# LED_driverV1.net
KiCad netlist of a schematic drawn in EAGLE
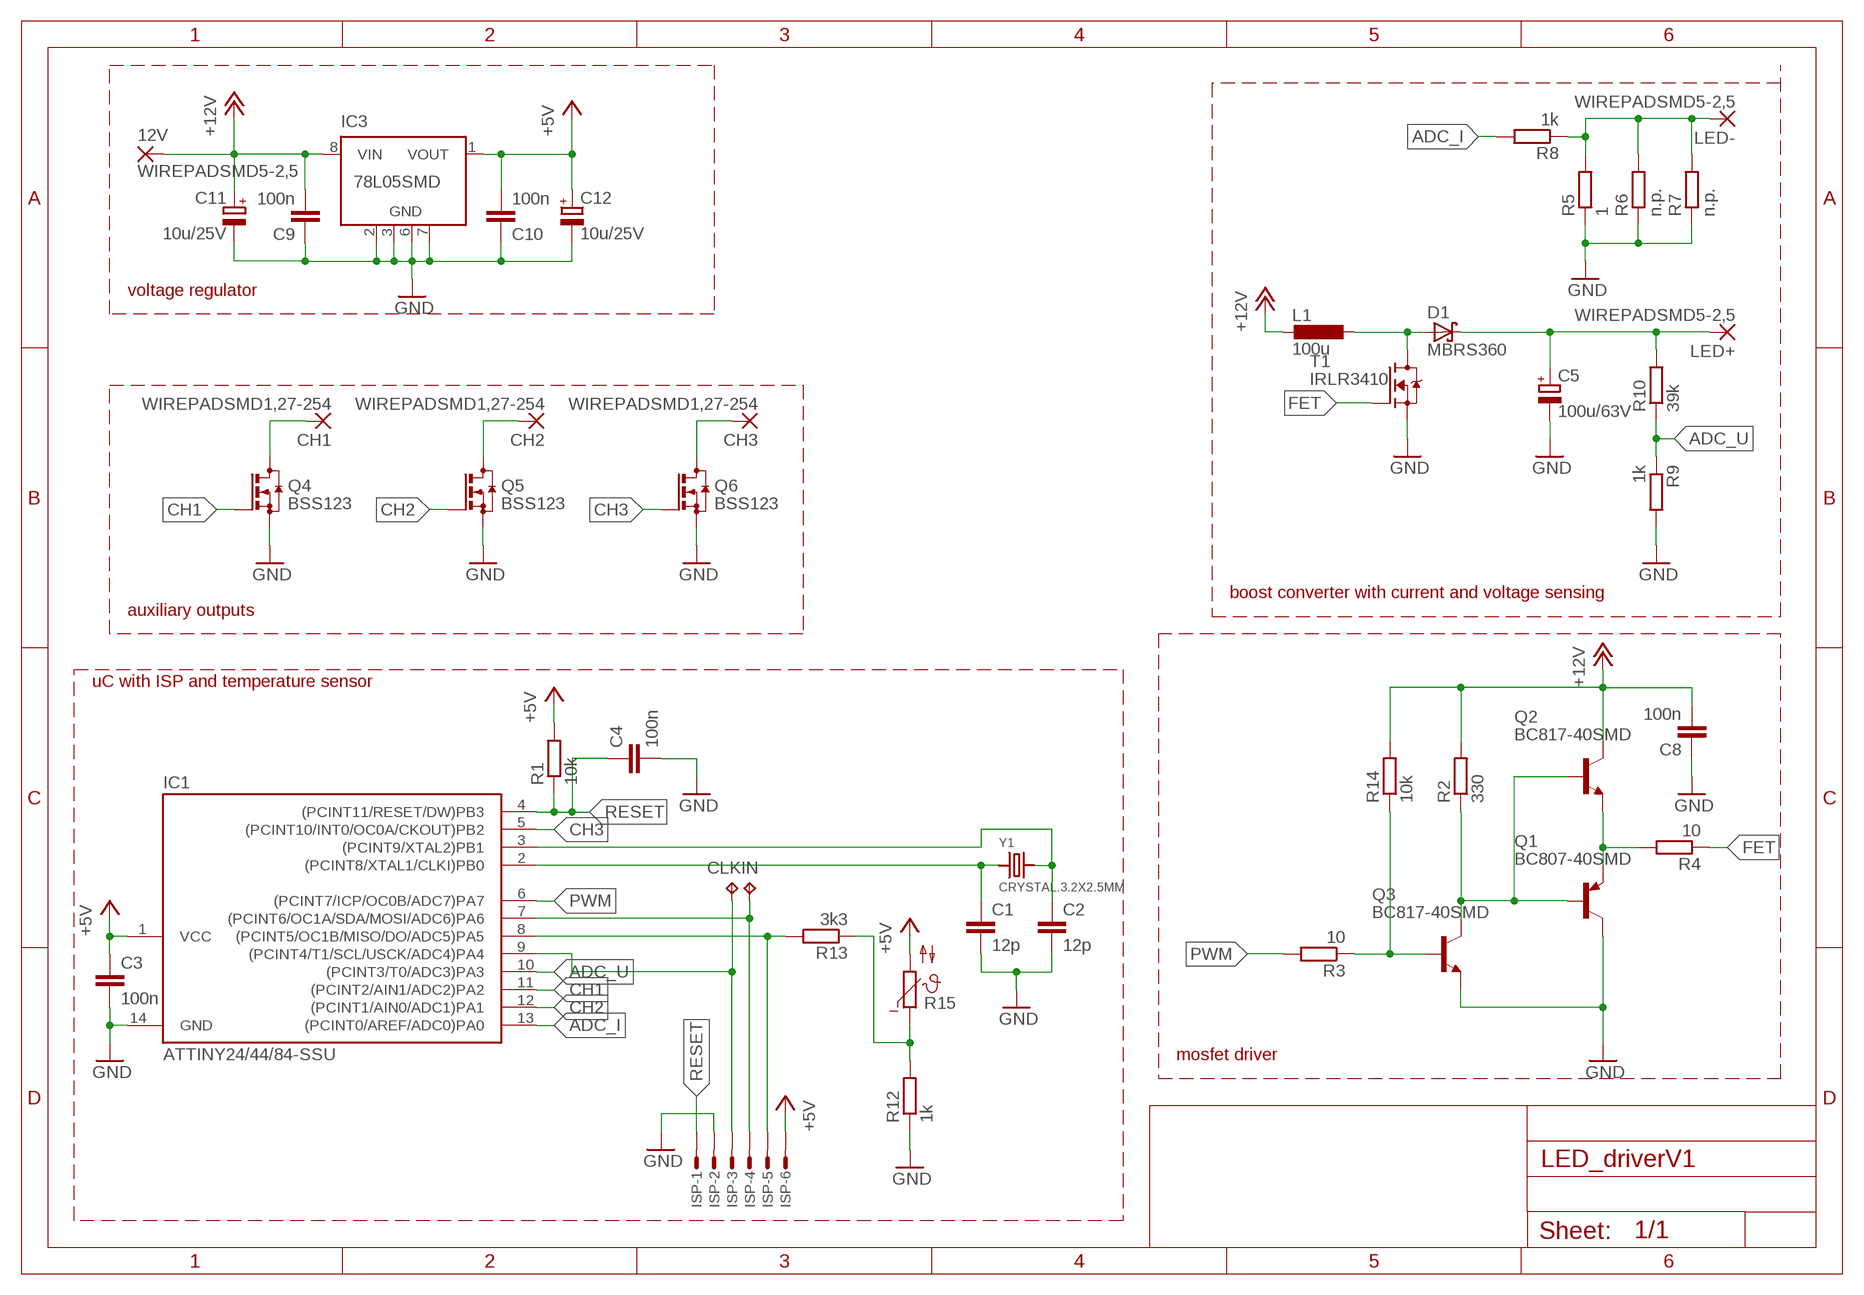
[diagram p0: schematic, sheet 1]

(export (version "E")
  (design (tool "Eeschema 10.0.6"))
  (components
    (comp (ref "12V")
      (value "WIREPADSMD5-2,5")
      (footprint "eagle-import:5-2,5")
      (libsource (lib "eagle-import") (part "WIREPADSMD5-2,5"))
    )
    (comp (ref "C1")
      (value "12p")
      (footprint "eagle-import:C0603K")
      (libsource (lib "eagle-import") (part "C-EUC0603K"))
    )
    (comp (ref "C2")
      (value "12p")
      (footprint "eagle-import:C0603K")
      (libsource (lib "eagle-import") (part "C-EUC0603K"))
    )
    (comp (ref "C3")
      (value "100n")
      (footprint "eagle-import:C0603K")
      (libsource (lib "eagle-import") (part "C-EUC0603K"))
    )
    (comp (ref "C4")
      (value "100n")
      (footprint "eagle-import:C0603K")
      (libsource (lib "eagle-import") (part "C-EUC0603K"))
    )
    (comp (ref "C5")
      (value "100u/63V")
      (footprint "eagle-import:153CLV-1010")
      (libsource (lib "eagle-import") (part "CPOL-EU153CLV-1010"))
    )
    (comp (ref "C8")
      (value "100n")
      (footprint "eagle-import:C0603K")
      (libsource (lib "eagle-import") (part "C-EUC0603K"))
    )
    (comp (ref "C9")
      (value "100n")
      (footprint "eagle-import:C0603K")
      (libsource (lib "eagle-import") (part "C-EUC0603K"))
    )
    (comp (ref "C10")
      (value "100n")
      (footprint "eagle-import:C0603K")
      (libsource (lib "eagle-import") (part "C-EUC0603K"))
    )
    (comp (ref "C11")
      (value "10u/25V")
      (footprint "eagle-import:153CLV-0405")
      (libsource (lib "eagle-import") (part "CPOL-EU153CLV-0405"))
    )
    (comp (ref "C12")
      (value "10u/25V")
      (footprint "eagle-import:153CLV-0405")
      (libsource (lib "eagle-import") (part "CPOL-EU153CLV-0405"))
    )
    (comp (ref "CH1")
      (value "WIREPADSMD1,27-254")
      (footprint "eagle-import:SMD1,27-2,54")
      (libsource (lib "eagle-import") (part "WIREPADSMD1,27-254"))
    )
    (comp (ref "CH2")
      (value "WIREPADSMD1,27-254")
      (footprint "eagle-import:SMD1,27-2,54")
      (libsource (lib "eagle-import") (part "WIREPADSMD1,27-254"))
    )
    (comp (ref "CH3")
      (value "WIREPADSMD1,27-254")
      (footprint "eagle-import:SMD1,27-2,54")
      (libsource (lib "eagle-import") (part "WIREPADSMD1,27-254"))
    )
    (comp (ref "CLK")
      (value "TPTP15R")
      (footprint "eagle-import:TP15R")
      (libsource (lib "eagle-import") (part "TPTP15R"))
    )
    (comp (ref "D1")
      (value "MBRS360")
      (footprint "eagle-import:SMC")
      (libsource (lib "eagle-import") (part "SCHOTTKY-DIODESMC"))
    )
    (comp (ref "IC1")
      (value "ATTINY24/44/84-SSU")
      (footprint "eagle-import:SOIC14")
      (libsource (lib "eagle-import") (part "ATTINY24/44/84-SSU"))
    )
    (comp (ref "IC3")
      (value "78L05SMD")
      (footprint "eagle-import:SO08")
      (libsource (lib "eagle-import") (part "78LSMD05"))
    )
    (comp (ref "IN")
      (value "TPTP15R")
      (footprint "eagle-import:TP15R")
      (libsource (lib "eagle-import") (part "TPTP15R"))
    )
    (comp (ref "ISP")
      (value "MICROMATCH-6SMF")
      (footprint "eagle-import:MMT-F-SMD-6")
      (libsource (lib "eagle-import") (part "MICROMATCH-6SMF"))
    )
    (comp (ref "L1")
      (value "100u")
      (footprint "eagle-import:PISM")
      (libsource (lib "eagle-import") (part "L-EUPISM"))
    )
    (comp (ref "LED+")
      (value "WIREPADSMD5-2,5")
      (footprint "eagle-import:5-2,5")
      (libsource (lib "eagle-import") (part "WIREPADSMD5-2,5"))
    )
    (comp (ref "LED-")
      (value "WIREPADSMD5-2,5")
      (footprint "eagle-import:5-2,5")
      (libsource (lib "eagle-import") (part "WIREPADSMD5-2,5"))
    )
    (comp (ref "Q1")
      (value "BC807-40SMD")
      (footprint "eagle-import:SOT23-BEC")
      (libsource (lib "eagle-import") (part "BC807SMD-40"))
    )
    (comp (ref "Q2")
      (value "BC817-40SMD")
      (footprint "eagle-import:SOT23-BEC")
      (libsource (lib "eagle-import") (part "BC817SMD-40"))
    )
    (comp (ref "Q3")
      (value "BC817-40SMD")
      (footprint "eagle-import:SOT23-BEC")
      (libsource (lib "eagle-import") (part "BC817SMD-40"))
    )
    (comp (ref "Q4")
      (value "BSS123")
      (footprint "eagle-import:SOT23")
      (libsource (lib "eagle-import") (part "BSS123"))
    )
    (comp (ref "Q5")
      (value "BSS123")
      (footprint "eagle-import:SOT23")
      (libsource (lib "eagle-import") (part "BSS123"))
    )
    (comp (ref "Q6")
      (value "BSS123")
      (footprint "eagle-import:SOT23")
      (libsource (lib "eagle-import") (part "BSS123"))
    )
    (comp (ref "R1")
      (value "10k")
      (footprint "eagle-import:R0603")
      (libsource (lib "eagle-import") (part "R-EU_R0603"))
    )
    (comp (ref "R2")
      (value "330")
      (footprint "eagle-import:R0603")
      (libsource (lib "eagle-import") (part "R-EU_R0603"))
    )
    (comp (ref "R3")
      (value "10")
      (footprint "eagle-import:R0603")
      (libsource (lib "eagle-import") (part "R-EU_R0603"))
    )
    (comp (ref "R4")
      (value "10")
      (footprint "eagle-import:R0603")
      (libsource (lib "eagle-import") (part "R-EU_R0603"))
    )
    (comp (ref "R5")
      (value "1")
      (footprint "eagle-import:R1206")
      (libsource (lib "eagle-import") (part "resistor_R-EU_R1206"))
    )
    (comp (ref "R6")
      (value "n.p.")
      (footprint "eagle-import:R1206")
      (libsource (lib "eagle-import") (part "resistor_R-EU_R1206"))
    )
    (comp (ref "R7")
      (value "n.p.")
      (footprint "eagle-import:R1206")
      (libsource (lib "eagle-import") (part "resistor_R-EU_R1206"))
    )
    (comp (ref "R8")
      (value "1k")
      (footprint "eagle-import:R0603")
      (libsource (lib "eagle-import") (part "R-EU_R0603"))
    )
    (comp (ref "R9")
      (value "1k")
      (footprint "eagle-import:R0603")
      (libsource (lib "eagle-import") (part "R-EU_R0603"))
    )
    (comp (ref "R10")
      (value "39k")
      (footprint "eagle-import:R0603")
      (libsource (lib "eagle-import") (part "R-EU_R0603"))
    )
    (comp (ref "R12")
      (value "1k")
      (footprint "eagle-import:R0603")
      (libsource (lib "eagle-import") (part "R-EU_R0603"))
    )
    (comp (ref "R13")
      (value "3k3")
      (footprint "eagle-import:R0603")
      (libsource (lib "eagle-import") (part "R-EU_R0603"))
    )
    (comp (ref "R14")
      (value "10k")
      (footprint "eagle-import:R0603")
      (libsource (lib "eagle-import") (part "R-EU_R0603"))
    )
    (comp (ref "R15")
      (value "NTC640")
      (footprint "eagle-import:P640")
      (libsource (lib "eagle-import") (part "NTC640"))
    )
    (comp (ref "T1")
      (value "IRLR3410")
      (footprint "eagle-import:TO252")
      (libsource (lib "eagle-import") (part "IRLR3410"))
    )
    (comp (ref "Y1")
      (value "CRYSTAL.3.2X2.5MM")
      (footprint "eagle-import:3.2X2.5MM")
      (libsource (lib "eagle-import") (part "CRYSTAL.3.2X2.5MM"))
    )
  )
  (nets
    (net (code "1") (name "+5V") (class "Default")
      (node (ref "C10") (pin "2") (pinfunction "2_2") (pintype "passive"))
      (node (ref "C12") (pin "+") (pinfunction "+_+") (pintype "passive"))
      (node (ref "C3") (pin "1") (pinfunction "1_1") (pintype "passive"))
      (node (ref "IC1") (pin "1") (pinfunction "VCC_1") (pintype "power_in"))
      (node (ref "IC3") (pin "1") (pinfunction "VOUT_1") (pintype "output"))
      (node (ref "ISP") (pin "6") (pinfunction "S_6") (pintype "passive"))
      (node (ref "R1") (pin "2") (pinfunction "2_2") (pintype "passive"))
      (node (ref "R15") (pin "2") (pinfunction "2_2") (pintype "passive"))
    )
    (net (code "2") (name "+12V") (class "Default")
      (node (ref "12V") (pin "1") (pinfunction "P_1") (pintype "passive"))
      (node (ref "C11") (pin "+") (pinfunction "+_+") (pintype "passive"))
      (node (ref "C8") (pin "2") (pinfunction "2_2") (pintype "passive"))
      (node (ref "C9") (pin "2") (pinfunction "2_2") (pintype "passive"))
      (node (ref "IC3") (pin "8") (pinfunction "VIN_8") (pintype "passive"))
      (node (ref "L1") (pin "2") (pinfunction "2_2") (pintype "passive"))
      (node (ref "Q2") (pin "C") (pinfunction "C_C") (pintype "passive"))
      (node (ref "R14") (pin "2") (pinfunction "2_2") (pintype "passive"))
      (node (ref "R2") (pin "2") (pinfunction "2_2") (pintype "passive"))
    )
    (net (code "3") (name "ADC_I") (class "Default")
      (node (ref "IC1") (pin "13") (pinfunction "(PCINT0/AREF/ADC0)PA0_13") (pintype "bidirectional"))
      (node (ref "R8") (pin "2") (pinfunction "2_2") (pintype "passive"))
    )
    (net (code "4") (name "ADC_U") (class "Default")
      (node (ref "IC1") (pin "10") (pinfunction "(PCINT3/T0/ADC3)PA3_10") (pintype "bidirectional"))
      (node (ref "R10") (pin "1") (pinfunction "1_1") (pintype "passive"))
      (node (ref "R9") (pin "1") (pinfunction "1_1") (pintype "passive"))
    )
    (net (code "5") (name "CH1") (class "Default")
      (node (ref "IC1") (pin "11") (pinfunction "(PCINT2/AIN1/ADC2)PA2_11") (pintype "bidirectional"))
      (node (ref "Q4") (pin "1") (pinfunction "G_1") (pintype "passive"))
    )
    (net (code "6") (name "CH2") (class "Default")
      (node (ref "IC1") (pin "12") (pinfunction "(PCINT1/AIN0/ADC1)PA1_12") (pintype "bidirectional"))
      (node (ref "Q5") (pin "1") (pinfunction "G_1") (pintype "passive"))
    )
    (net (code "7") (name "CH3") (class "Default")
      (node (ref "IC1") (pin "5") (pinfunction "(PCINT10/INT0/OC0A/CKOUT)PB2_5") (pintype "bidirectional"))
      (node (ref "Q6") (pin "1") (pinfunction "G_1") (pintype "passive"))
    )
    (net (code "8") (name "FET") (class "Default")
      (node (ref "R4") (pin "1") (pinfunction "1_1") (pintype "passive"))
      (node (ref "T1") (pin "1") (pinfunction "G_1") (pintype "passive"))
    )
    (net (code "9") (name "GND") (class "Default")
      (node (ref "C1") (pin "2") (pinfunction "2_2") (pintype "passive"))
      (node (ref "C10") (pin "1") (pinfunction "1_1") (pintype "passive"))
      (node (ref "C11") (pin "-") (pinfunction "-_-") (pintype "passive"))
      (node (ref "C12") (pin "-") (pinfunction "-_-") (pintype "passive"))
      (node (ref "C2") (pin "2") (pinfunction "2_2") (pintype "passive"))
      (node (ref "C3") (pin "2") (pinfunction "2_2") (pintype "passive"))
      (node (ref "C4") (pin "2") (pinfunction "2_2") (pintype "passive"))
      (node (ref "C5") (pin "-") (pinfunction "-_-") (pintype "passive"))
      (node (ref "C8") (pin "1") (pinfunction "1_1") (pintype "passive"))
      (node (ref "C9") (pin "1") (pinfunction "1_1") (pintype "passive"))
      (node (ref "IC1") (pin "14") (pinfunction "GND_14") (pintype "power_in"))
      (node (ref "IC3") (pin "2") (pinfunction "GND_2") (pintype "power_in"))
      (node (ref "IC3") (pin "3") (pinfunction "GND_3") (pintype "power_in"))
      (node (ref "IC3") (pin "6") (pinfunction "GND_6") (pintype "power_in"))
      (node (ref "IC3") (pin "7") (pinfunction "GND_7") (pintype "power_in"))
      (node (ref "ISP") (pin "2") (pinfunction "S_2") (pintype "passive"))
      (node (ref "Q1") (pin "C") (pinfunction "C_C") (pintype "passive"))
      (node (ref "Q3") (pin "E") (pinfunction "E_E") (pintype "passive"))
      (node (ref "Q4") (pin "2") (pinfunction "S_2") (pintype "passive"))
      (node (ref "Q5") (pin "2") (pinfunction "S_2") (pintype "passive"))
      (node (ref "Q6") (pin "2") (pinfunction "S_2") (pintype "passive"))
      (node (ref "R12") (pin "1") (pinfunction "1_1") (pintype "passive"))
      (node (ref "R5") (pin "1") (pinfunction "1_1") (pintype "passive"))
      (node (ref "R6") (pin "1") (pinfunction "1_1") (pintype "passive"))
      (node (ref "R7") (pin "1") (pinfunction "1_1") (pintype "passive"))
      (node (ref "R9") (pin "2") (pinfunction "2_2") (pintype "passive"))
      (node (ref "T1") (pin "2") (pinfunction "S_2") (pintype "passive"))
    )
    (net (code "10") (name "Net-(CH1-P)") (class "Default")
      (node (ref "CH1") (pin "1") (pinfunction "P_1") (pintype "passive"))
      (node (ref "Q4") (pin "3") (pinfunction "D_3") (pintype "passive"))
    )
    (net (code "11") (name "Net-(CH2-P)") (class "Default")
      (node (ref "CH2") (pin "1") (pinfunction "P_1") (pintype "passive"))
      (node (ref "Q5") (pin "3") (pinfunction "D_3") (pintype "passive"))
    )
    (net (code "12") (name "Net-(CH3-P)") (class "Default")
      (node (ref "CH3") (pin "1") (pinfunction "P_1") (pintype "passive"))
      (node (ref "Q6") (pin "3") (pinfunction "D_3") (pintype "passive"))
    )
    (net (code "13") (name "Net-(IC1-(PCINT4{slash}T1{slash}SCL{slash}USCK{slash}ADC4)PA4)") (class "Default")
      (node (ref "CLK") (pin "TP") (pinfunction "TP_TP") (pintype "input"))
      (node (ref "IC1") (pin "9") (pinfunction "(PCINT4/T1/SCL/USCK/ADC4)PA4_9") (pintype "bidirectional"))
      (node (ref "ISP") (pin "3") (pinfunction "S_3") (pintype "passive"))
    )
    (net (code "14") (name "Net-(IC1-(PCINT5{slash}OC1B{slash}MISO{slash}DO{slash}ADC5)PA5)") (class "Default")
      (node (ref "IC1") (pin "8") (pinfunction "(PCINT5/OC1B/MISO/DO/ADC5)PA5_8") (pintype "bidirectional"))
      (node (ref "ISP") (pin "5") (pinfunction "S_5") (pintype "passive"))
      (node (ref "R13") (pin "2") (pinfunction "2_2") (pintype "passive"))
    )
    (net (code "15") (name "Net-(IC1-(PCINT6{slash}OC1A{slash}SDA{slash}MOSI{slash}ADC6)PA6)") (class "Default")
      (node (ref "IC1") (pin "7") (pinfunction "(PCINT6/OC1A/SDA/MOSI/ADC6)PA6_7") (pintype "bidirectional"))
      (node (ref "IN") (pin "TP") (pinfunction "TP_TP") (pintype "input"))
      (node (ref "ISP") (pin "4") (pinfunction "S_4") (pintype "passive"))
    )
    (net (code "16") (name "Net-(IC1-(PCINT8{slash}XTAL1{slash}CLKI)PB0)") (class "Default")
      (node (ref "C1") (pin "1") (pinfunction "1_1") (pintype "passive"))
      (node (ref "IC1") (pin "2") (pinfunction "(PCINT8/XTAL1/CLKI)PB0_2") (pintype "bidirectional"))
      (node (ref "Y1") (pin "1") (pinfunction "1_1") (pintype "passive"))
    )
    (net (code "17") (name "Net-(IC1-(PCINT9{slash}XTAL2)PB1)") (class "Default")
      (node (ref "C2") (pin "1") (pinfunction "1_1") (pintype "passive"))
      (node (ref "IC1") (pin "3") (pinfunction "(PCINT9/XTAL2)PB1_3") (pintype "bidirectional"))
      (node (ref "Y1") (pin "3") (pinfunction "2_3") (pintype "passive"))
    )
    (net (code "18") (name "Net-(LED+-P)") (class "Default")
      (node (ref "C5") (pin "+") (pinfunction "+_+") (pintype "passive"))
      (node (ref "D1") (pin "C") (pinfunction "C_C") (pintype "passive"))
      (node (ref "LED+") (pin "1") (pinfunction "P_1") (pintype "passive"))
      (node (ref "R10") (pin "2") (pinfunction "2_2") (pintype "passive"))
    )
    (net (code "19") (name "Net-(LED--P)") (class "Default")
      (node (ref "LED-") (pin "1") (pinfunction "P_1") (pintype "passive"))
      (node (ref "R5") (pin "2") (pinfunction "2_2") (pintype "passive"))
      (node (ref "R6") (pin "2") (pinfunction "2_2") (pintype "passive"))
      (node (ref "R7") (pin "2") (pinfunction "2_2") (pintype "passive"))
      (node (ref "R8") (pin "1") (pinfunction "1_1") (pintype "passive"))
    )
    (net (code "20") (name "Net-(Q1-PadB)") (class "Default")
      (node (ref "Q1") (pin "B") (pinfunction "B_B") (pintype "passive"))
      (node (ref "Q2") (pin "B") (pinfunction "B_B") (pintype "passive"))
      (node (ref "Q3") (pin "C") (pinfunction "C_C") (pintype "passive"))
      (node (ref "R2") (pin "1") (pinfunction "1_1") (pintype "passive"))
    )
    (net (code "21") (name "Net-(Q1-PadE)") (class "Default")
      (node (ref "Q1") (pin "E") (pinfunction "E_E") (pintype "passive"))
      (node (ref "Q2") (pin "E") (pinfunction "E_E") (pintype "passive"))
      (node (ref "R4") (pin "2") (pinfunction "2_2") (pintype "passive"))
    )
    (net (code "22") (name "Net-(Q3-PadB)") (class "Default")
      (node (ref "Q3") (pin "B") (pinfunction "B_B") (pintype "passive"))
      (node (ref "R14") (pin "1") (pinfunction "1_1") (pintype "passive"))
      (node (ref "R3") (pin "1") (pinfunction "1_1") (pintype "passive"))
    )
    (net (code "23") (name "Net-(R12-Pad2)") (class "Default")
      (node (ref "R12") (pin "2") (pinfunction "2_2") (pintype "passive"))
      (node (ref "R13") (pin "1") (pinfunction "1_1") (pintype "passive"))
      (node (ref "R15") (pin "1") (pinfunction "1_1") (pintype "passive"))
    )
    (net (code "24") (name "Net-(T1-D)") (class "Default")
      (node (ref "D1") (pin "A") (pinfunction "A_A") (pintype "passive"))
      (node (ref "L1") (pin "1") (pinfunction "1_1") (pintype "passive"))
      (node (ref "T1") (pin "3") (pinfunction "D_3") (pintype "passive"))
    )
    (net (code "25") (name "PWM") (class "Default")
      (node (ref "IC1") (pin "6") (pinfunction "(PCINT7/ICP/OC0B/ADC7)PA7_6") (pintype "bidirectional"))
      (node (ref "R3") (pin "2") (pinfunction "2_2") (pintype "passive"))
    )
    (net (code "26") (name "RESET") (class "Default")
      (node (ref "C4") (pin "1") (pinfunction "1_1") (pintype "passive"))
      (node (ref "IC1") (pin "4") (pinfunction "(PCINT11/RESET/DW)PB3_4") (pintype "bidirectional"))
      (node (ref "ISP") (pin "1") (pinfunction "S_1") (pintype "passive"))
      (node (ref "R1") (pin "1") (pinfunction "1_1") (pintype "passive"))
    )
  )
)
